# Sheet1.net
KiCad netlist of a schematic drawn in Altium Designer
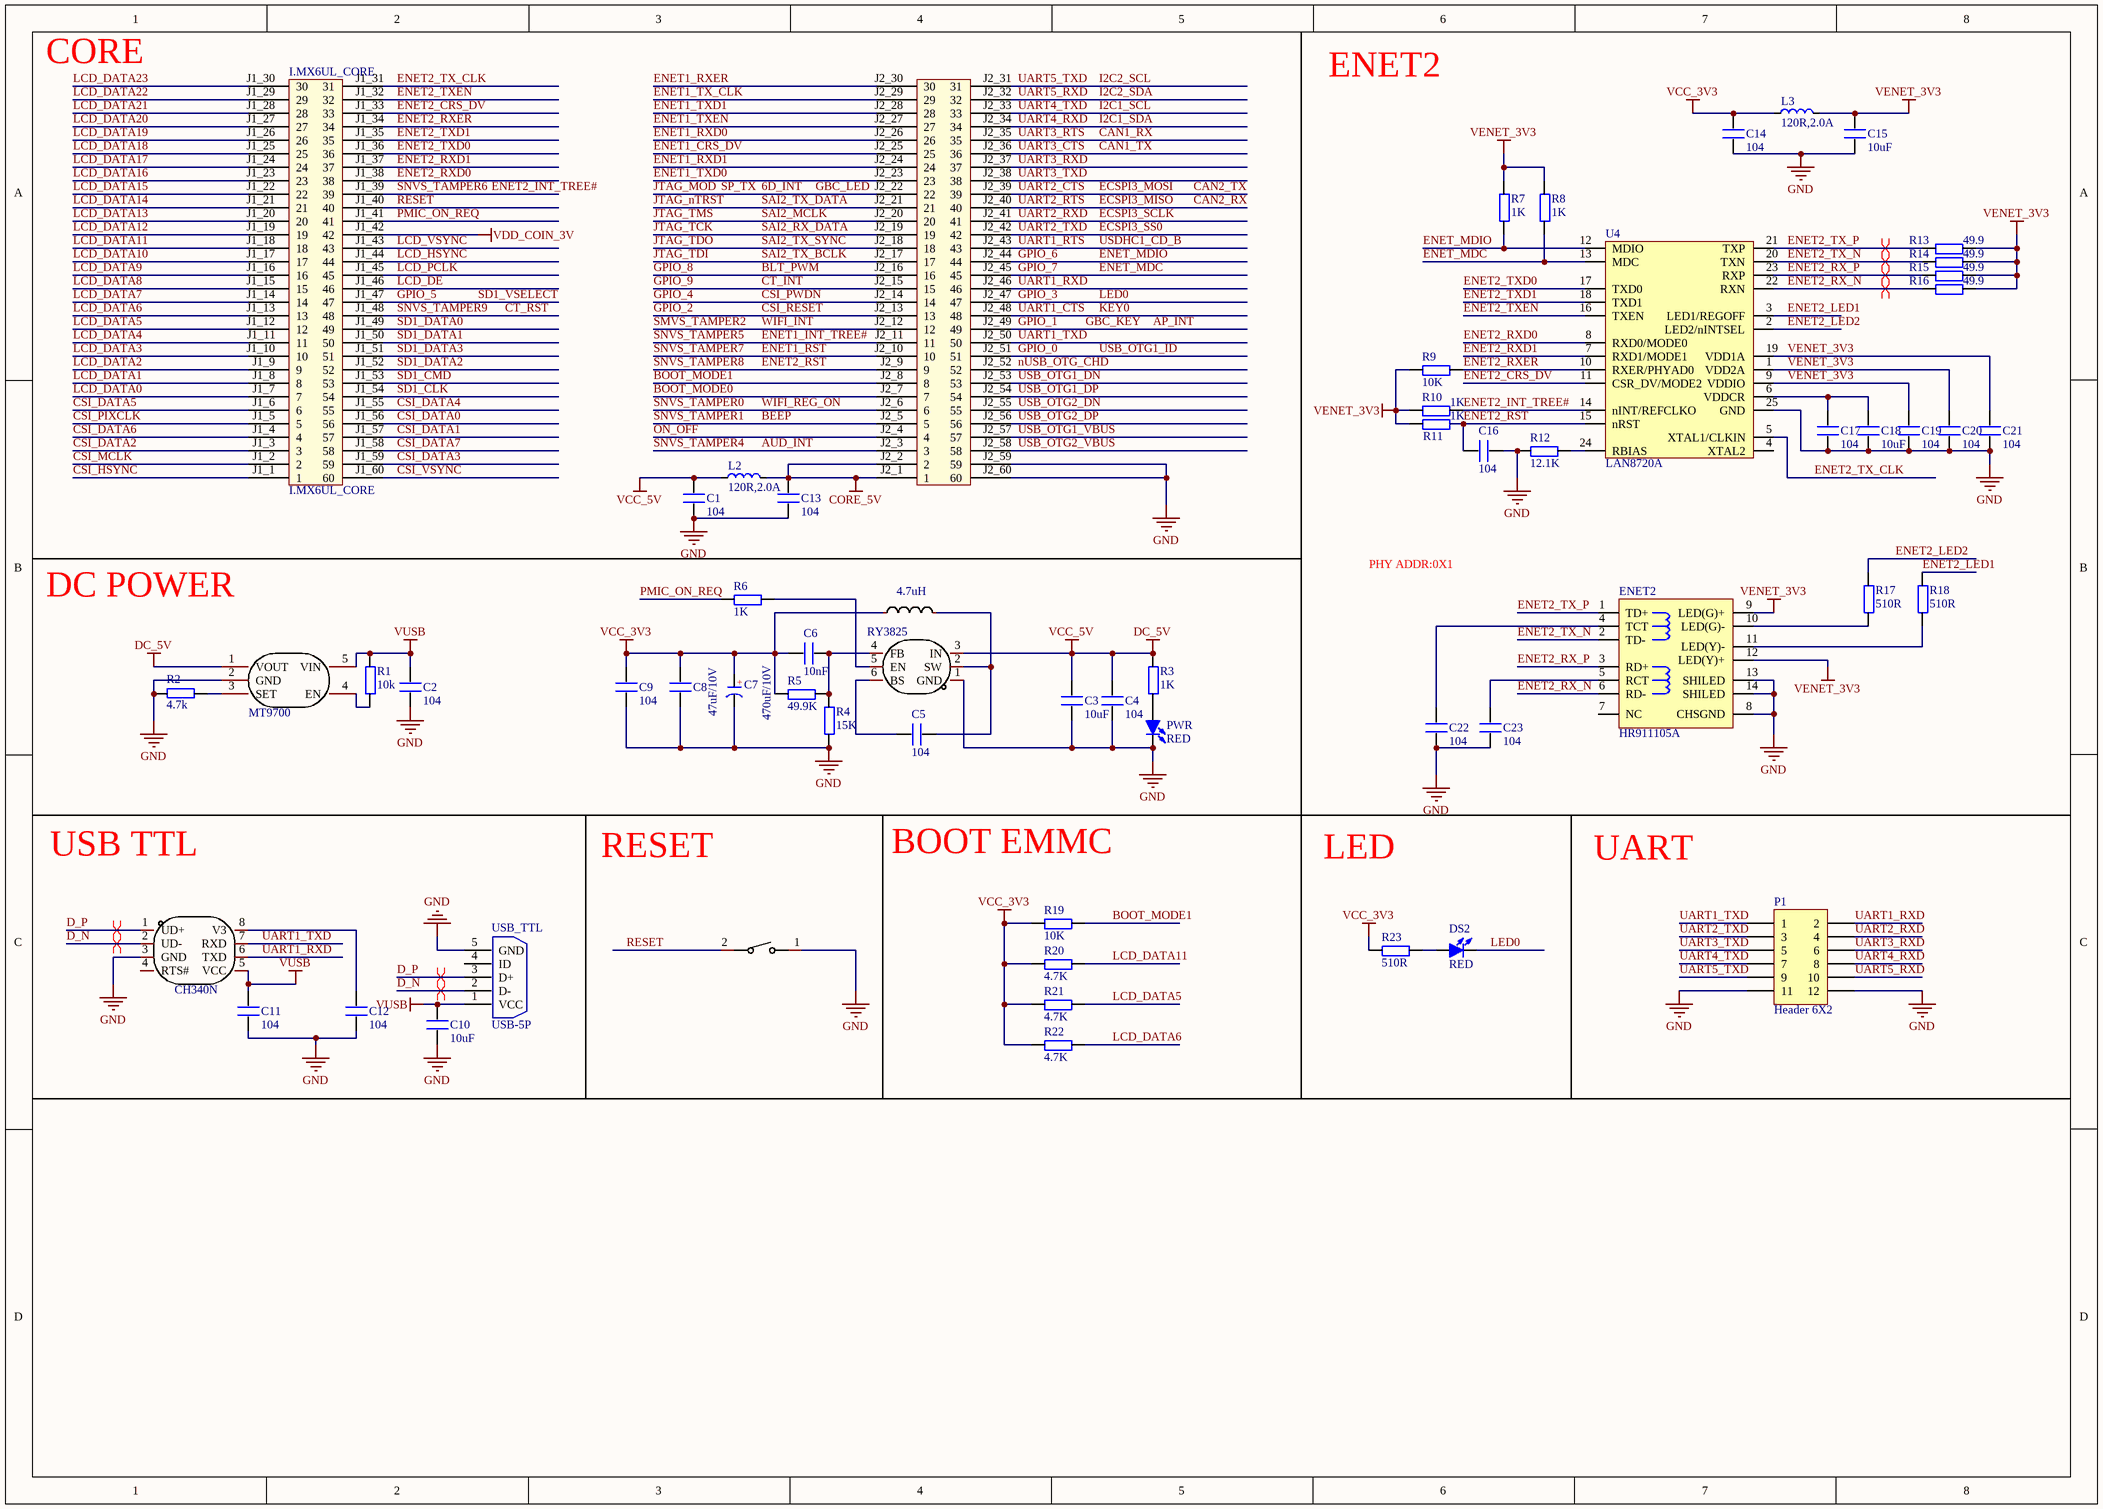
[diagram p0: Sheet1.SchDoc]

(export (version "E")
  (design (tool "Eeschema 10.0.6"))
  (components
    (comp (ref "1")
      (value "4.7uH")
      (footprint "IND-SMD_L5.4-W5.2_FXL0530")
      (description "4.7uH 5A")
      (fields (field (name "MANUFACTURER") "cjiang(长江微电)") (field (name "MANUFACTURER PART") "FXL0530-4R7-M"))
      (libsource (lib "LC_Components") (part "FXL0530-4R7-M"))
    )
    (comp (ref "C1") (value "104") (footprint "C 0603") (libsource (lib "IMX6UL_ALPHA(底板)_V2.0") (part "C")))
    (comp (ref "C2") (value "104") (footprint "C 0603") (libsource (lib "IMX6UL_ALPHA(底板)_V2.0") (part "C")))
    (comp (ref "C3") (value "10uF") (footprint "C 0603") (libsource (lib "IMX6UL_ALPHA(底板)_V2.0") (part "C")))
    (comp (ref "C4") (value "104") (footprint "C 0603") (libsource (lib "IMX6UL_ALPHA(底板)_V2.0") (part "C")))
    (comp (ref "C5") (value "104") (footprint "C 0603") (libsource (lib "IMX6UL_ALPHA(底板)_V2.0") (part "C")))
    (comp (ref "C6") (value "10nF") (footprint "C 0603") (libsource (lib "IMX6UL_ALPHA(底板)_V2.0") (part "C")))
    (comp (ref "C7")
      (value "470uF/10V")
      (footprint "CM D(6.3*7.7)")
      (description "贴片电解电容")
      (fields (field (name "版权归属") "源创客"))
      (libsource (lib "IMX6UL_ALPHA(底板)_V2.0") (part "C-CM"))
    )
    (comp (ref "C8")
      (value "47uF/10V")
      (footprint "1206")
      (libsource (lib "IMX6UL_ALPHA(底板)_V2.0") (part "C"))
    )
    (comp (ref "C9") (value "104") (footprint "C 0603") (libsource (lib "IMX6UL_ALPHA(底板)_V2.0") (part "C")))
    (comp (ref "C10")
      (value "10uF")
      (footprint "C 0603")
      (libsource (lib "IMX6UL_ALPHA(底板)_V2.0") (part "C"))
    )
    (comp (ref "C11") (value "104") (footprint "C 0603") (libsource (lib "IMX6UL_ALPHA(底板)_V2.0") (part "C")))
    (comp (ref "C12") (value "104") (footprint "C 0603") (libsource (lib "IMX6UL_ALPHA(底板)_V2.0") (part "C")))
    (comp (ref "C13") (value "104") (footprint "C 0603") (libsource (lib "IMX6UL_ALPHA(底板)_V2.0") (part "C")))
    (comp (ref "C14") (value "104") (footprint "C 0603") (libsource (lib "IMX6UL_ALPHA(底板)_V2.0") (part "C")))
    (comp (ref "C15")
      (value "10uF")
      (footprint "C 0603")
      (libsource (lib "IMX6UL_ALPHA(底板)_V2.0") (part "C"))
    )
    (comp (ref "C16") (value "104") (footprint "C 0603") (libsource (lib "IMX6UL_ALPHA(底板)_V2.0") (part "C")))
    (comp (ref "C17") (value "104") (footprint "C 0603") (libsource (lib "IMX6UL_ALPHA(底板)_V2.0") (part "C")))
    (comp (ref "C18")
      (value "10uF")
      (footprint "C 0603")
      (libsource (lib "IMX6UL_ALPHA(底板)_V2.0") (part "C"))
    )
    (comp (ref "C19") (value "104") (footprint "C 0603") (libsource (lib "IMX6UL_ALPHA(底板)_V2.0") (part "C")))
    (comp (ref "C20") (value "104") (footprint "C 0603") (libsource (lib "IMX6UL_ALPHA(底板)_V2.0") (part "C")))
    (comp (ref "C21") (value "104") (footprint "C 0603") (libsource (lib "IMX6UL_ALPHA(底板)_V2.0") (part "C")))
    (comp (ref "C22") (value "104") (footprint "C 0603") (libsource (lib "IMX6UL_ALPHA(底板)_V2.0") (part "C")))
    (comp (ref "C23") (value "104") (footprint "C 0603") (libsource (lib "IMX6UL_ALPHA(底板)_V2.0") (part "C")))
    (comp (ref "DS2")
      (value "RED")
      (footprint "LED 0603B")
      (description "贴片LED")
      (fields (field (name "版权归属") "源创客"))
      (libsource (lib "IMX6UL_ALPHA(底板)_V2.0") (part "LED-SMD"))
    )
    (comp (ref "ENET2")
      (value "HR911105A")
      (footprint "RJ-45A12")
      (description "带灯以太网接口")
      (fields (field (name "版权归属") "源创客"))
      (libsource (lib "IMX6UL_ALPHA(底板)_V2.0") (part "HR911105A"))
    )
    (comp (ref "I.MX6UL_CORE")
      (value "I.MX6UL_CORE")
      (footprint "I.MX6UL_CORE")
      (description "I.MX6UL核心板")
      (libsource (lib "IMX6UL_ALPHA(底板)_V2.0") (part "I.MX6UL核心板"))
    )
    (comp (ref "L2")
      (value "120R,2.0A")
      (footprint "L 0603")
      (description "小功率贴片电感磁珠")
      (fields (field (name "版权归属") "源创客"))
      (libsource (lib "IMX6UL_ALPHA(底板)_V2.0") (part "L"))
    )
    (comp (ref "L3")
      (value "120R,2.0A")
      (footprint "L 0603")
      (description "小功率贴片电感磁珠")
      (fields (field (name "版权归属") "源创客"))
      (libsource (lib "IMX6UL_ALPHA(底板)_V2.0") (part "L"))
    )
    (comp (ref "P1")
      (value "Header 6X2")
      (footprint "HDR2X6")
      (description "Header, 6-Pin, Dual row")
      (fields (field (name "PUBLISHER") "Altium Limited"))
      (libsource (lib "IMX6UL_ALPHA(底板)_V2.0") (part "Header 6X2"))
    )
    (comp (ref "PWR")
      (value "RED")
      (footprint "LED 0603B")
      (description "贴片LED")
      (fields (field (name "版权归属") "源创客"))
      (libsource (lib "IMX6UL_ALPHA(底板)_V2.0") (part "LED-SMD"))
    )
    (comp (ref "R1") (value "10k") (footprint "R 0603") (libsource (lib "IMX6UL_ALPHA(底板)_V2.0") (part "R")))
    (comp (ref "R2") (value "4.7k") (footprint "R 0603") (libsource (lib "IMX6UL_ALPHA(底板)_V2.0") (part "R")))
    (comp (ref "R3") (value "1K") (footprint "R 0603") (libsource (lib "IMX6UL_ALPHA(底板)_V2.0") (part "R")))
    (comp (ref "R4") (value "15K") (footprint "R 0603") (libsource (lib "IMX6UL_ALPHA(底板)_V2.0") (part "R")))
    (comp (ref "R5")
      (value "49.9K")
      (footprint "R 0603")
      (libsource (lib "IMX6UL_ALPHA(底板)_V2.0") (part "R"))
    )
    (comp (ref "R6") (value "1K") (footprint "R 0603") (libsource (lib "IMX6UL_ALPHA(底板)_V2.0") (part "R")))
    (comp (ref "R7") (value "1K") (footprint "R 0603") (libsource (lib "IMX6UL_ALPHA(底板)_V2.0") (part "R")))
    (comp (ref "R8") (value "1K") (footprint "R 0603") (libsource (lib "IMX6UL_ALPHA(底板)_V2.0") (part "R")))
    (comp (ref "R9") (value "10K") (footprint "R 0603") (libsource (lib "IMX6UL_ALPHA(底板)_V2.0") (part "R")))
    (comp (ref "R10") (value "1K") (footprint "R 0603") (libsource (lib "IMX6UL_ALPHA(底板)_V2.0") (part "R")))
    (comp (ref "R11") (value "1K") (footprint "R 0603") (libsource (lib "IMX6UL_ALPHA(底板)_V2.0") (part "R")))
    (comp (ref "R12")
      (value "12.1K")
      (footprint "R 0603")
      (libsource (lib "IMX6UL_ALPHA(底板)_V2.0") (part "R"))
    )
    (comp (ref "R13")
      (value "49.9")
      (footprint "R 0603")
      (libsource (lib "IMX6UL_ALPHA(底板)_V2.0") (part "R"))
    )
    (comp (ref "R14")
      (value "49.9")
      (footprint "R 0603")
      (libsource (lib "IMX6UL_ALPHA(底板)_V2.0") (part "R"))
    )
    (comp (ref "R15")
      (value "49.9")
      (footprint "R 0603")
      (libsource (lib "IMX6UL_ALPHA(底板)_V2.0") (part "R"))
    )
    (comp (ref "R16")
      (value "49.9")
      (footprint "R 0603")
      (libsource (lib "IMX6UL_ALPHA(底板)_V2.0") (part "R"))
    )
    (comp (ref "R17")
      (value "510R")
      (footprint "R 0603")
      (libsource (lib "IMX6UL_ALPHA(底板)_V2.0") (part "R"))
    )
    (comp (ref "R18")
      (value "510R")
      (footprint "R 0603")
      (libsource (lib "IMX6UL_ALPHA(底板)_V2.0") (part "R"))
    )
    (comp (ref "R19") (value "10K") (footprint "R 0603") (libsource (lib "IMX6UL_ALPHA(底板)_V2.0") (part "R")))
    (comp (ref "R20")
      (value "4.7K")
      (footprint "R 0603")
      (libsource (lib "IMX6UL_ALPHA(底板)_V2.0") (part "R"))
    )
    (comp (ref "R21")
      (value "4.7K")
      (footprint "R 0603")
      (libsource (lib "IMX6UL_ALPHA(底板)_V2.0") (part "R"))
    )
    (comp (ref "R22")
      (value "4.7K")
      (footprint "R 0603")
      (libsource (lib "IMX6UL_ALPHA(底板)_V2.0") (part "R"))
    )
    (comp (ref "R23")
      (value "510R")
      (footprint "R 0603")
      (libsource (lib "IMX6UL_ALPHA(底板)_V2.0") (part "R"))
    )
    (comp (ref "SW")
      (value "TS3625A-HT")
      (footprint "SW-SMD_L6.1-W3.7-LS7.9")
      (description "红头按键")
      (fields (field (name "MANUFACTURER") "SHOU HAN(首韩)"))
      (libsource (lib "LC_Components") (part "TS3625A-HT"))
    )
    (comp (ref "U1")
      (value "MT9700")
      (footprint "SOT-23-5_L3.0-W1.7-P0.95-LS2.8-BR")
      (fields (field (name "MANUFACTURER") "西安航天民芯"))
      (libsource (lib "LC_Components") (part "MT9700"))
    )
    (comp (ref "U2")
      (value "RY3825")
      (footprint "SOT-23-6_L2.9-W1.6-P0.95-LS2.8-BR")
      (fields (field (name "MANUFACTURER") "RYCHiP(蕊源)"))
      (libsource (lib "LC_Components") (part "RY3825"))
    )
    (comp (ref "U3")
      (value "CH340N")
      (footprint "SOP-8_L4.9-W3.9-P1.27-LS6.0-BL")
      (fields (field (name "DESIGNER") "U?"))
      (libsource (lib "LC_Components") (part "CH340N_C2977777"))
    )
    (comp (ref "U4")
      (value "LAN8720A")
      (footprint "QFN24")
      (description "ETH PHY")
      (libsource (lib "IMX6UL_ALPHA(底板)_V2.0") (part "LAN8720"))
    )
    (comp (ref "USB_TTL")
      (value "USB-5P")
      (footprint "USB-MINI-A")
      (description "微型USB母座")
      (fields (field (name "版权归属") "源创客"))
      (libsource (lib "IMX6UL_ALPHA(底板)_V2.0") (part "USB-5P"))
    )
  )
  (nets
    (net (code "1") (name "/6D_INT") (class "Default")
      (node (ref "I.MX6UL_CORE") (pin "J2_22") (pinfunction "22_J2_22") (pintype "passive"))
    )
    (net (code "2") (name "/AP_INT") (class "Default")
      (node (ref "I.MX6UL_CORE") (pin "J2_49") (pinfunction "49_J2_49") (pintype "passive"))
    )
    (net (code "3") (name "/AUD_INT") (class "Default")
      (node (ref "I.MX6UL_CORE") (pin "J2_3") (pinfunction "3_J2_3") (pintype "passive"))
    )
    (net (code "4") (name "/BEEP") (class "Default")
      (node (ref "I.MX6UL_CORE") (pin "J2_5") (pinfunction "5_J2_5") (pintype "passive"))
    )
    (net (code "5") (name "/BLT_PWM") (class "Default")
      (node (ref "I.MX6UL_CORE") (pin "J2_16") (pinfunction "16_J2_16") (pintype "passive"))
    )
    (net (code "6") (name "/BOOT_MODE0") (class "Default")
      (node (ref "I.MX6UL_CORE") (pin "J2_7") (pinfunction "7_J2_7") (pintype "passive"))
    )
    (net (code "7") (name "/BOOT_MODE1") (class "Default")
      (node (ref "I.MX6UL_CORE") (pin "J2_8") (pinfunction "8_J2_8") (pintype "passive"))
      (node (ref "R19") (pin "2") (pintype "passive"))
    )
    (net (code "8") (name "/CAN1_RX") (class "Default")
      (node (ref "I.MX6UL_CORE") (pin "J2_35") (pinfunction "35_J2_35") (pintype "passive"))
    )
    (net (code "9") (name "/CAN1_TX") (class "Default")
      (node (ref "I.MX6UL_CORE") (pin "J2_36") (pinfunction "36_J2_36") (pintype "passive"))
    )
    (net (code "10") (name "/CAN2_RX") (class "Default")
      (node (ref "I.MX6UL_CORE") (pin "J2_40") (pinfunction "40_J2_40") (pintype "passive"))
    )
    (net (code "11") (name "/CAN2_TX") (class "Default")
      (node (ref "I.MX6UL_CORE") (pin "J2_39") (pinfunction "39_J2_39") (pintype "passive"))
    )
    (net (code "12") (name "/CSI_DATA0") (class "Default")
      (node (ref "I.MX6UL_CORE") (pin "J1_56") (pinfunction "56_J1_56") (pintype "passive"))
    )
    (net (code "13") (name "/CSI_DATA1") (class "Default")
      (node (ref "I.MX6UL_CORE") (pin "J1_57") (pinfunction "57_J1_57") (pintype "passive"))
    )
    (net (code "14") (name "/CSI_DATA2") (class "Default")
      (node (ref "I.MX6UL_CORE") (pin "J1_3") (pinfunction "3_J1_3") (pintype "passive"))
    )
    (net (code "15") (name "/CSI_DATA3") (class "Default")
      (node (ref "I.MX6UL_CORE") (pin "J1_59") (pinfunction "59_J1_59") (pintype "passive"))
    )
    (net (code "16") (name "/CSI_DATA4") (class "Default")
      (node (ref "I.MX6UL_CORE") (pin "J1_55") (pinfunction "55_J1_55") (pintype "passive"))
    )
    (net (code "17") (name "/CSI_DATA5") (class "Default")
      (node (ref "I.MX6UL_CORE") (pin "J1_6") (pinfunction "6_J1_6") (pintype "passive"))
    )
    (net (code "18") (name "/CSI_DATA6") (class "Default")
      (node (ref "I.MX6UL_CORE") (pin "J1_4") (pinfunction "4_J1_4") (pintype "passive"))
    )
    (net (code "19") (name "/CSI_DATA7") (class "Default")
      (node (ref "I.MX6UL_CORE") (pin "J1_58") (pinfunction "58_J1_58") (pintype "passive"))
    )
    (net (code "20") (name "/CSI_HSYNC") (class "Default")
      (node (ref "I.MX6UL_CORE") (pin "J1_1") (pinfunction "1_J1_1") (pintype "passive"))
    )
    (net (code "21") (name "/CSI_MCLK") (class "Default")
      (node (ref "I.MX6UL_CORE") (pin "J1_2") (pinfunction "2_J1_2") (pintype "passive"))
    )
    (net (code "22") (name "/CSI_PIXCLK") (class "Default")
      (node (ref "I.MX6UL_CORE") (pin "J1_5") (pinfunction "5_J1_5") (pintype "passive"))
    )
    (net (code "23") (name "/CSI_PWDN") (class "Default")
      (node (ref "I.MX6UL_CORE") (pin "J2_14") (pinfunction "14_J2_14") (pintype "passive"))
    )
    (net (code "24") (name "/CSI_RESET") (class "Default")
      (node (ref "I.MX6UL_CORE") (pin "J2_13") (pinfunction "13_J2_13") (pintype "passive"))
    )
    (net (code "25") (name "/CSI_VSYNC") (class "Default")
      (node (ref "I.MX6UL_CORE") (pin "J1_60") (pinfunction "60_J1_60") (pintype "passive"))
    )
    (net (code "26") (name "/CT_INT") (class "Default")
      (node (ref "I.MX6UL_CORE") (pin "J2_15") (pinfunction "15_J2_15") (pintype "passive"))
    )
    (net (code "27") (name "/CT_RST") (class "Default")
      (node (ref "I.MX6UL_CORE") (pin "J1_48") (pinfunction "48_J1_48") (pintype "passive"))
    )
    (net (code "28") (name "/D_N") (class "Default")
      (node (ref "U3") (pin "2") (pinfunction "UD-_2") (pintype "passive"))
      (node (ref "USB_TTL") (pin "2") (pinfunction "D-_2") (pintype "passive"))
    )
    (net (code "29") (name "/D_P") (class "Default")
      (node (ref "U3") (pin "1") (pinfunction "UD+_1") (pintype "passive"))
      (node (ref "USB_TTL") (pin "3") (pinfunction "D+_3") (pintype "passive"))
    )
    (net (code "30") (name "/ECSPI3_SCLK") (class "Default")
      (node (ref "I.MX6UL_CORE") (pin "J2_41") (pinfunction "41_J2_41") (pintype "passive"))
      (node (ref "P1") (pin "4") (pinfunction "4_4") (pintype "passive"))
    )
    (net (code "31") (name "/ECSPI3_SS0") (class "Default")
      (node (ref "I.MX6UL_CORE") (pin "J2_42") (pinfunction "42_J2_42") (pintype "passive"))
      (node (ref "P1") (pin "3") (pinfunction "3_3") (pintype "passive"))
    )
    (net (code "32") (name "/ENET1_CRS_DV") (class "Default")
      (node (ref "I.MX6UL_CORE") (pin "J2_25") (pinfunction "25_J2_25") (pintype "passive"))
    )
    (net (code "33") (name "/ENET1_INT_TREE#") (class "Default")
      (node (ref "I.MX6UL_CORE") (pin "J2_11") (pinfunction "11_J2_11") (pintype "passive"))
    )
    (net (code "34") (name "/ENET1_RST") (class "Default")
      (node (ref "I.MX6UL_CORE") (pin "J2_10") (pinfunction "10_J2_10") (pintype "passive"))
    )
    (net (code "35") (name "/ENET1_RXD0") (class "Default")
      (node (ref "I.MX6UL_CORE") (pin "J2_26") (pinfunction "26_J2_26") (pintype "passive"))
    )
    (net (code "36") (name "/ENET1_RXD1") (class "Default")
      (node (ref "I.MX6UL_CORE") (pin "J2_24") (pinfunction "24_J2_24") (pintype "passive"))
    )
    (net (code "37") (name "/ENET1_RXER") (class "Default")
      (node (ref "I.MX6UL_CORE") (pin "J2_30") (pinfunction "30_J2_30") (pintype "passive"))
    )
    (net (code "38") (name "/ENET1_TXD0") (class "Default")
      (node (ref "I.MX6UL_CORE") (pin "J2_23") (pinfunction "23_J2_23") (pintype "passive"))
    )
    (net (code "39") (name "/ENET1_TXD1") (class "Default")
      (node (ref "I.MX6UL_CORE") (pin "J2_28") (pinfunction "28_J2_28") (pintype "passive"))
    )
    (net (code "40") (name "/ENET1_TXEN") (class "Default")
      (node (ref "I.MX6UL_CORE") (pin "J2_27") (pinfunction "27_J2_27") (pintype "passive"))
    )
    (net (code "41") (name "/ENET1_TX_CLK") (class "Default")
      (node (ref "I.MX6UL_CORE") (pin "J2_29") (pinfunction "29_J2_29") (pintype "passive"))
    )
    (net (code "42") (name "/ENET2_CRS_DV") (class "Default")
      (node (ref "I.MX6UL_CORE") (pin "J1_33") (pinfunction "33_J1_33") (pintype "passive"))
      (node (ref "U4") (pin "11") (pinfunction "CSR_DV/MODE2_11") (pintype "passive"))
    )
    (net (code "43") (name "/ENET2_INT_TREE#") (class "Default")
      (node (ref "I.MX6UL_CORE") (pin "J1_39") (pinfunction "39_J1_39") (pintype "passive"))
      (node (ref "R10") (pin "2") (pintype "passive"))
      (node (ref "U4") (pin "14") (pinfunction "nINT/REFCLKO_14") (pintype "passive"))
    )
    (net (code "44") (name "/ENET2_LED1") (class "Default")
      (node (ref "R18") (pin "2") (pintype "passive"))
      (node (ref "U4") (pin "3") (pinfunction "LED1/REGOFF_3") (pintype "passive"))
    )
    (net (code "45") (name "/ENET2_LED2") (class "Default")
      (node (ref "R17") (pin "2") (pintype "passive"))
      (node (ref "U4") (pin "2") (pinfunction "LED2/nINTSEL_2") (pintype "passive"))
    )
    (net (code "46") (name "/ENET2_RST") (class "Default")
      (node (ref "C16") (pin "1") (pintype "passive"))
      (node (ref "I.MX6UL_CORE") (pin "J2_9") (pinfunction "9_J2_9") (pintype "passive"))
      (node (ref "R11") (pin "2") (pintype "passive"))
      (node (ref "U4") (pin "15") (pinfunction "nRST_15") (pintype "passive"))
    )
    (net (code "47") (name "/ENET2_RXD0") (class "Default")
      (node (ref "I.MX6UL_CORE") (pin "J1_38") (pinfunction "38_J1_38") (pintype "passive"))
      (node (ref "U4") (pin "8") (pinfunction "RXD0/MODE0_8") (pintype "passive"))
    )
    (net (code "48") (name "/ENET2_RXD1") (class "Default")
      (node (ref "I.MX6UL_CORE") (pin "J1_37") (pinfunction "37_J1_37") (pintype "passive"))
      (node (ref "U4") (pin "7") (pinfunction "RXD1/MODE1_7") (pintype "passive"))
    )
    (net (code "49") (name "/ENET2_RXER") (class "Default")
      (node (ref "I.MX6UL_CORE") (pin "J1_34") (pinfunction "34_J1_34") (pintype "passive"))
      (node (ref "R9") (pin "2") (pintype "passive"))
      (node (ref "U4") (pin "10") (pinfunction "RXER/PHYAD0_10") (pintype "passive"))
    )
    (net (code "50") (name "/ENET2_RX_N") (class "Default")
      (node (ref "ENET2") (pin "6") (pinfunction "RD-_6") (pintype "passive"))
      (node (ref "R16") (pin "1") (pintype "passive"))
      (node (ref "U4") (pin "22") (pinfunction "RXN_22") (pintype "passive"))
    )
    (net (code "51") (name "/ENET2_RX_P") (class "Default")
      (node (ref "ENET2") (pin "3") (pinfunction "RD+_3") (pintype "passive"))
      (node (ref "R15") (pin "1") (pintype "passive"))
      (node (ref "U4") (pin "23") (pinfunction "RXP_23") (pintype "passive"))
    )
    (net (code "52") (name "/ENET2_TXD0") (class "Default")
      (node (ref "I.MX6UL_CORE") (pin "J1_36") (pinfunction "36_J1_36") (pintype "passive"))
      (node (ref "U4") (pin "17") (pinfunction "TXD0_17") (pintype "passive"))
    )
    (net (code "53") (name "/ENET2_TXD1") (class "Default")
      (node (ref "I.MX6UL_CORE") (pin "J1_35") (pinfunction "35_J1_35") (pintype "passive"))
      (node (ref "U4") (pin "18") (pinfunction "TXD1_18") (pintype "passive"))
    )
    (net (code "54") (name "/ENET2_TXEN") (class "Default")
      (node (ref "I.MX6UL_CORE") (pin "J1_32") (pinfunction "32_J1_32") (pintype "passive"))
      (node (ref "U4") (pin "16") (pinfunction "TXEN_16") (pintype "passive"))
    )
    (net (code "55") (name "/ENET2_TX_CLK") (class "Default")
      (node (ref "I.MX6UL_CORE") (pin "J1_31") (pinfunction "31_J1_31") (pintype "passive"))
      (node (ref "U4") (pin "5") (pinfunction "XTAL1/CLKIN_5") (pintype "passive"))
    )
    (net (code "56") (name "/ENET2_TX_N") (class "Default")
      (node (ref "ENET2") (pin "2") (pinfunction "TD-_2") (pintype "passive"))
      (node (ref "R14") (pin "1") (pintype "passive"))
      (node (ref "U4") (pin "20") (pinfunction "TXN_20") (pintype "passive"))
    )
    (net (code "57") (name "/ENET2_TX_P") (class "Default")
      (node (ref "ENET2") (pin "1") (pinfunction "TD+_1") (pintype "passive"))
      (node (ref "R13") (pin "1") (pintype "passive"))
      (node (ref "U4") (pin "21") (pinfunction "TXP_21") (pintype "passive"))
    )
    (net (code "58") (name "/ENET_MDC") (class "Default")
      (node (ref "I.MX6UL_CORE") (pin "J2_45") (pinfunction "45_J2_45") (pintype "passive"))
      (node (ref "R8") (pin "1") (pintype "passive"))
      (node (ref "U4") (pin "13") (pinfunction "MDC_13") (pintype "passive"))
    )
    (net (code "59") (name "/ENET_MDIO") (class "Default")
      (node (ref "I.MX6UL_CORE") (pin "J2_44") (pinfunction "44_J2_44") (pintype "passive"))
      (node (ref "R7") (pin "1") (pintype "passive"))
      (node (ref "U4") (pin "12") (pinfunction "MDIO_12") (pintype "passive"))
    )
    (net (code "60") (name "/GPIO_0") (class "Default")
      (node (ref "I.MX6UL_CORE") (pin "J2_51") (pinfunction "51_J2_51") (pintype "passive"))
    )
    (net (code "61") (name "/GPIO_3") (class "Default")
      (node (ref "DS2") (pin "2") (pinfunction "K_2") (pintype "passive"))
      (node (ref "I.MX6UL_CORE") (pin "J2_47") (pinfunction "47_J2_47") (pintype "passive"))
    )
    (net (code "62") (name "/GPIO_5") (class "Default")
      (node (ref "I.MX6UL_CORE") (pin "J1_47") (pinfunction "47_J1_47") (pintype "passive"))
    )
    (net (code "63") (name "/I2C1_SCL") (class "Default")
      (node (ref "I.MX6UL_CORE") (pin "J2_33") (pinfunction "33_J2_33") (pintype "passive"))
      (node (ref "P1") (pin "7") (pinfunction "7_7") (pintype "passive"))
    )
    (net (code "64") (name "/I2C1_SDA") (class "Default")
      (node (ref "I.MX6UL_CORE") (pin "J2_34") (pinfunction "34_J2_34") (pintype "passive"))
      (node (ref "P1") (pin "8") (pinfunction "8_8") (pintype "passive"))
    )
    (net (code "65") (name "/I2C2_SCL") (class "Default")
      (node (ref "I.MX6UL_CORE") (pin "J2_31") (pinfunction "31_J2_31") (pintype "passive"))
      (node (ref "P1") (pin "9") (pinfunction "9_9") (pintype "passive"))
    )
    (net (code "66") (name "/I2C2_SDA") (class "Default")
      (node (ref "I.MX6UL_CORE") (pin "J2_32") (pinfunction "32_J2_32") (pintype "passive"))
      (node (ref "P1") (pin "10") (pinfunction "10_10") (pintype "passive"))
    )
    (net (code "67") (name "/JTAG_TCK") (class "Default")
      (node (ref "I.MX6UL_CORE") (pin "J2_19") (pinfunction "19_J2_19") (pintype "passive"))
    )
    (net (code "68") (name "/JTAG_TDI") (class "Default")
      (node (ref "I.MX6UL_CORE") (pin "J2_17") (pinfunction "17_J2_17") (pintype "passive"))
    )
    (net (code "69") (name "/JTAG_TDO") (class "Default")
      (node (ref "I.MX6UL_CORE") (pin "J2_18") (pinfunction "18_J2_18") (pintype "passive"))
    )
    (net (code "70") (name "/JTAG_TMS") (class "Default")
      (node (ref "I.MX6UL_CORE") (pin "J2_20") (pinfunction "20_J2_20") (pintype "passive"))
    )
    (net (code "71") (name "/JTAG_nTRST") (class "Default")
      (node (ref "I.MX6UL_CORE") (pin "J2_21") (pinfunction "21_J2_21") (pintype "passive"))
    )
    (net (code "72") (name "/KEY0") (class "Default")
      (node (ref "I.MX6UL_CORE") (pin "J2_48") (pinfunction "48_J2_48") (pintype "passive"))
    )
    (net (code "73") (name "/LCD_DATA0") (class "Default")
      (node (ref "I.MX6UL_CORE") (pin "J1_7") (pinfunction "7_J1_7") (pintype "passive"))
    )
    (net (code "74") (name "/LCD_DATA1") (class "Default")
      (node (ref "I.MX6UL_CORE") (pin "J1_8") (pinfunction "8_J1_8") (pintype "passive"))
    )
    (net (code "75") (name "/LCD_DATA2") (class "Default")
      (node (ref "I.MX6UL_CORE") (pin "J1_9") (pinfunction "9_J1_9") (pintype "passive"))
    )
    (net (code "76") (name "/LCD_DATA3") (class "Default")
      (node (ref "I.MX6UL_CORE") (pin "J1_10") (pinfunction "10_J1_10") (pintype "passive"))
    )
    (net (code "77") (name "/LCD_DATA4") (class "Default")
      (node (ref "I.MX6UL_CORE") (pin "J1_11") (pinfunction "11_J1_11") (pintype "passive"))
    )
    (net (code "78") (name "/LCD_DATA5") (class "Default")
      (node (ref "I.MX6UL_CORE") (pin "J1_12") (pinfunction "12_J1_12") (pintype "passive"))
      (node (ref "R21") (pin "2") (pintype "passive"))
    )
    (net (code "79") (name "/LCD_DATA6") (class "Default")
      (node (ref "I.MX6UL_CORE") (pin "J1_13") (pinfunction "13_J1_13") (pintype "passive"))
      (node (ref "R22") (pin "2") (pintype "passive"))
    )
    (net (code "80") (name "/LCD_DATA7") (class "Default")
      (node (ref "I.MX6UL_CORE") (pin "J1_14") (pinfunction "14_J1_14") (pintype "passive"))
    )
    (net (code "81") (name "/LCD_DATA8") (class "Default")
      (node (ref "I.MX6UL_CORE") (pin "J1_15") (pinfunction "15_J1_15") (pintype "passive"))
    )
    (net (code "82") (name "/LCD_DATA9") (class "Default")
      (node (ref "I.MX6UL_CORE") (pin "J1_16") (pinfunction "16_J1_16") (pintype "passive"))
    )
    (net (code "83") (name "/LCD_DATA10") (class "Default")
      (node (ref "I.MX6UL_CORE") (pin "J1_17") (pinfunction "17_J1_17") (pintype "passive"))
    )
    (net (code "84") (name "/LCD_DATA11") (class "Default")
      (node (ref "I.MX6UL_CORE") (pin "J1_18") (pinfunction "18_J1_18") (pintype "passive"))
      (node (ref "R20") (pin "2") (pintype "passive"))
    )
    (net (code "85") (name "/LCD_DATA12") (class "Default")
      (node (ref "I.MX6UL_CORE") (pin "J1_19") (pinfunction "19_J1_19") (pintype "passive"))
    )
    (net (code "86") (name "/LCD_DATA13") (class "Default")
      (node (ref "I.MX6UL_CORE") (pin "J1_20") (pinfunction "20_J1_20") (pintype "passive"))
    )
    (net (code "87") (name "/LCD_DATA14") (class "Default")
      (node (ref "I.MX6UL_CORE") (pin "J1_21") (pinfunction "21_J1_21") (pintype "passive"))
    )
    (net (code "88") (name "/LCD_DATA15") (class "Default")
      (node (ref "I.MX6UL_CORE") (pin "J1_22") (pinfunction "22_J1_22") (pintype "passive"))
    )
    (net (code "89") (name "/LCD_DATA16") (class "Default")
      (node (ref "I.MX6UL_CORE") (pin "J1_23") (pinfunction "23_J1_23") (pintype "passive"))
    )
    (net (code "90") (name "/LCD_DATA17") (class "Default")
      (node (ref "I.MX6UL_CORE") (pin "J1_24") (pinfunction "24_J1_24") (pintype "passive"))
    )
    (net (code "91") (name "/LCD_DATA18") (class "Default")
      (node (ref "I.MX6UL_CORE") (pin "J1_25") (pinfunction "25_J1_25") (pintype "passive"))
    )
    (net (code "92") (name "/LCD_DATA19") (class "Default")
      (node (ref "I.MX6UL_CORE") (pin "J1_26") (pinfunction "26_J1_26") (pintype "passive"))
    )
    (net (code "93") (name "/LCD_DATA20") (class "Default")
      (node (ref "I.MX6UL_CORE") (pin "J1_27") (pinfunction "27_J1_27") (pintype "passive"))
    )
    (net (code "94") (name "/LCD_DATA21") (class "Default")
      (node (ref "I.MX6UL_CORE") (pin "J1_28") (pinfunction "28_J1_28") (pintype "passive"))
    )
    (net (code "95") (name "/LCD_DATA22") (class "Default")
      (node (ref "I.MX6UL_CORE") (pin "J1_29") (pinfunction "29_J1_29") (pintype "passive"))
    )
    (net (code "96") (name "/LCD_DATA23") (class "Default")
      (node (ref "I.MX6UL_CORE") (pin "J1_30") (pinfunction "30_J1_30") (pintype "passive"))
    )
    (net (code "97") (name "/LCD_DE") (class "Default")
      (node (ref "I.MX6UL_CORE") (pin "J1_46") (pinfunction "46_J1_46") (pintype "passive"))
    )
    (net (code "98") (name "/LCD_HSYNC") (class "Default")
      (node (ref "I.MX6UL_CORE") (pin "J1_44") (pinfunction "44_J1_44") (pintype "passive"))
    )
    (net (code "99") (name "/LCD_PCLK") (class "Default")
      (node (ref "I.MX6UL_CORE") (pin "J1_45") (pinfunction "45_J1_45") (pintype "passive"))
    )
    (net (code "100") (name "/LCD_VSYNC") (class "Default")
      (node (ref "I.MX6UL_CORE") (pin "J1_43") (pinfunction "43_J1_43") (pintype "passive"))
    )
    (net (code "101") (name "/ON_OFF") (class "Default")
      (node (ref "I.MX6UL_CORE") (pin "J2_4") (pinfunction "4_J2_4") (pintype "passive"))
    )
    (net (code "102") (name "/PMIC_ON_REQ") (class "Default")
      (node (ref "I.MX6UL_CORE") (pin "J1_41") (pinfunction "41_J1_41") (pintype "passive"))
      (node (ref "R6") (pin "1") (pintype "passive"))
    )
    (net (code "103") (name "/RESET") (class "Default")
      (node (ref "I.MX6UL_CORE") (pin "J1_40") (pinfunction "40_J1_40") (pintype "passive"))
      (node (ref "SW") (pin "2") (pinfunction "B_2") (pintype "passive"))
    )
    (net (code "104") (name "/SD1_CLK") (class "Default")
      (node (ref "I.MX6UL_CORE") (pin "J1_54") (pinfunction "54_J1_54") (pintype "passive"))
    )
    (net (code "105") (name "/SD1_CMD") (class "Default")
      (node (ref "I.MX6UL_CORE") (pin "J1_53") (pinfunction "53_J1_53") (pintype "passive"))
    )
    (net (code "106") (name "/SD1_DATA0") (class "Default")
      (node (ref "I.MX6UL_CORE") (pin "J1_49") (pinfunction "49_J1_49") (pintype "passive"))
    )
    (net (code "107") (name "/SD1_DATA1") (class "Default")
      (node (ref "I.MX6UL_CORE") (pin "J1_50") (pinfunction "50_J1_50") (pintype "passive"))
    )
    (net (code "108") (name "/SD1_DATA2") (class "Default")
      (node (ref "I.MX6UL_CORE") (pin "J1_52") (pinfunction "52_J1_52") (pintype "passive"))
    )
    (net (code "109") (name "/SD1_DATA3") (class "Default")
      (node (ref "I.MX6UL_CORE") (pin "J1_51") (pinfunction "51_J1_51") (pintype "passive"))
    )
    (net (code "110") (name "/SMVS_TAMPER2") (class "Default")
      (node (ref "I.MX6UL_CORE") (pin "J2_12") (pinfunction "12_J2_12") (pintype "passive"))
    )
    (net (code "111") (name "/SNVS_TAMPER0") (class "Default")
      (node (ref "I.MX6UL_CORE") (pin "J2_6") (pinfunction "6_J2_6") (pintype "passive"))
    )
    (net (code "112") (name "/UART1_RTS") (class "Default")
      (node (ref "I.MX6UL_CORE") (pin "J2_43") (pinfunction "43_J2_43") (pintype "passive"))
    )
    (net (code "113") (name "/UART1_RXD") (class "Default")
      (node (ref "I.MX6UL_CORE") (pin "J2_46") (pinfunction "46_J2_46") (pintype "passive"))
      (node (ref "P1") (pin "2") (pinfunction "2_2") (pintype "passive"))
      (node (ref "U3") (pin "6") (pinfunction "TXD_6") (pintype "passive"))
    )
    (net (code "114") (name "/UART1_TXD") (class "Default")
      (node (ref "I.MX6UL_CORE") (pin "J2_50") (pinfunction "50_J2_50") (pintype "passive"))
      (node (ref "P1") (pin "1") (pinfunction "1_1") (pintype "passive"))
      (node (ref "U3") (pin "7") (pinfunction "RXD_7") (pintype "passive"))
    )
    (net (code "115") (name "/UART3_RXD") (class "Default")
      (node (ref "I.MX6UL_CORE") (pin "J2_37") (pinfunction "37_J2_37") (pintype "passive"))
      (node (ref "P1") (pin "6") (pinfunction "6_6") (pintype "passive"))
    )
    (net (code "116") (name "/UART3_TXD") (class "Default")
      (node (ref "I.MX6UL_CORE") (pin "J2_38") (pinfunction "38_J2_38") (pintype "passive"))
      (node (ref "P1") (pin "5") (pinfunction "5_5") (pintype "passive"))
    )
    (net (code "117") (name "/USB_OTG1_DN") (class "Default")
      (node (ref "I.MX6UL_CORE") (pin "J2_53") (pinfunction "53_J2_53") (pintype "passive"))
    )
    (net (code "118") (name "/USB_OTG1_DP") (class "Default")
      (node (ref "I.MX6UL_CORE") (pin "J2_54") (pinfunction "54_J2_54") (pintype "passive"))
    )
    (net (code "119") (name "/USB_OTG1_VBUS") (class "Default")
      (node (ref "I.MX6UL_CORE") (pin "J2_57") (pinfunction "57_J2_57") (pintype "passive"))
    )
    (net (code "120") (name "/USB_OTG2_DN") (class "Default")
      (node (ref "I.MX6UL_CORE") (pin "J2_55") (pinfunction "55_J2_55") (pintype "passive"))
    )
    (net (code "121") (name "/USB_OTG2_DP") (class "Default")
      (node (ref "I.MX6UL_CORE") (pin "J2_56") (pinfunction "56_J2_56") (pintype "passive"))
    )
    (net (code "122") (name "/USB_OTG2_VBUS") (class "Default")
      (node (ref "I.MX6UL_CORE") (pin "J2_58") (pinfunction "58_J2_58") (pintype "passive"))
    )
    (net (code "123") (name "/nUSB_OTG_CHD") (class "Default")
      (node (ref "I.MX6UL_CORE") (pin "J2_52") (pinfunction "52_J2_52") (pintype "passive"))
    )
    (net (code "124") (name "CORE_5V") (class "Default")
      (node (ref "C13") (pin "2") (pintype "passive"))
      (node (ref "I.MX6UL_CORE") (pin "J2_1") (pinfunction "1_J2_1") (pintype "passive"))
      (node (ref "I.MX6UL_CORE") (pin "J2_2") (pinfunction "2_J2_2") (pintype "passive"))
      (node (ref "L2") (pin "2") (pinfunction "2_2") (pintype "passive"))
    )
    (net (code "125") (name "DC_5V") (class "Default")
      (node (ref "C1") (pin "2") (pintype "passive"))
      (node (ref "C3") (pin "2") (pintype "passive"))
      (node (ref "C4") (pin "2") (pintype "passive"))
      (node (ref "L2") (pin "1") (pinfunction "1_1") (pintype "passive"))
      (node (ref "R3") (pin "2") (pintype "passive"))
      (node (ref "U1") (pin "1") (pinfunction "VOUT_1") (pintype "passive"))
      (node (ref "U2") (pin "3") (pinfunction "IN_3") (pintype "passive"))
    )
    (net (code "126") (name "GND") (class "Default")
      (node (ref "C1") (pin "1") (pintype "passive"))
      (node (ref "C10") (pin "1") (pintype "passive"))
      (node (ref "C11") (pin "1") (pintype "passive"))
      (node (ref "C12") (pin "1") (pintype "passive"))
      (node (ref "C13") (pin "1") (pintype "passive"))
      (node (ref "C14") (pin "1") (pintype "passive"))
      (node (ref "C15") (pin "1") (pintype "passive"))
      (node (ref "C16") (pin "2") (pintype "passive"))
      (node (ref "C17") (pin "1") (pintype "passive"))
      (node (ref "C18") (pin "1") (pintype "passive"))
      (node (ref "C19") (pin "1") (pintype "passive"))
      (node (ref "C2") (pin "1") (pintype "passive"))
      (node (ref "C20") (pin "1") (pintype "passive"))
      (node (ref "C21") (pin "1") (pintype "passive"))
      (node (ref "C22") (pin "1") (pintype "passive"))
      (node (ref "C23") (pin "1") (pintype "passive"))
      (node (ref "C3") (pin "1") (pintype "passive"))
      (node (ref "C4") (pin "1") (pintype "passive"))
      (node (ref "C7") (pin "2") (pinfunction "K_2") (pintype "passive"))
      (node (ref "C8") (pin "1") (pintype "passive"))
      (node (ref "C9") (pin "1") (pintype "passive"))
      (node (ref "ENET2") (pin "13") (pinfunction "SHILED_13") (pintype "passive"))
      (node (ref "ENET2") (pin "14") (pinfunction "SHILED_14") (pintype "passive"))
      (node (ref "ENET2") (pin "8") (pinfunction "CHSGND_8") (pintype "passive"))
      (node (ref "I.MX6UL_CORE") (pin "J2_59") (pinfunction "59_J2_59") (pintype "passive"))
      (node (ref "I.MX6UL_CORE") (pin "J2_60") (pinfunction "60_J2_60") (pintype "passive"))
      (node (ref "P1") (pin "11") (pinfunction "11_11") (pintype "passive"))
      (node (ref "P1") (pin "12") (pinfunction "12_12") (pintype "passive"))
      (node (ref "PWR") (pin "2") (pinfunction "K_2") (pintype "passive"))
      (node (ref "R12") (pin "1") (pintype "passive"))
      (node (ref "R2") (pin "2") (pintype "passive"))
      (node (ref "R4") (pin "1") (pintype "passive"))
      (node (ref "SW") (pin "1") (pinfunction "A_1") (pintype "passive"))
      (node (ref "U1") (pin "2") (pinfunction "GND_2") (pintype "passive"))
      (node (ref "U2") (pin "1") (pinfunction "GND_1") (pintype "passive"))
      (node (ref "U3") (pin "3") (pinfunction "GND_3") (pintype "passive"))
      (node (ref "U4") (pin "25") (pinfunction "GND_25") (pintype "passive"))
      (node (ref "USB_TTL") (pin "5") (pinfunction "GND_5") (pintype "passive"))
    )
    (net (code "127") (name "Net-(DS2-A)") (class "Default")
      (node (ref "DS2") (pin "1") (pinfunction "A_1") (pintype "passive"))
      (node (ref "R23") (pin "2") (pintype "passive"))
    )
    (net (code "128") (name "Net-(ENET2-LED(G)-)") (class "Default")
      (node (ref "ENET2") (pin "10") (pinfunction "LED(G)-_10") (pintype "passive"))
      (node (ref "R17") (pin "1") (pintype "passive"))
    )
    (net (code "129") (name "Net-(ENET2-LED(Y)-)") (class "Default")
      (node (ref "ENET2") (pin "11") (pinfunction "LED(Y)-_11") (pintype "passive"))
      (node (ref "R18") (pin "1") (pintype "passive"))
    )
    (net (code "130") (name "Net-(ENET2-RCT)") (class "Default")
      (node (ref "C23") (pin "2") (pintype "passive"))
      (node (ref "ENET2") (pin "5") (pinfunction "RCT_5") (pintype "passive"))
    )
    (net (code "131") (name "Net-(ENET2-TCT)") (class "Default")
      (node (ref "C22") (pin "2") (pintype "passive"))
      (node (ref "ENET2") (pin "4") (pinfunction "TCT_4") (pintype "passive"))
    )
    (net (code "132") (name "Net-(PWR-A)") (class "Default")
      (node (ref "PWR") (pin "1") (pinfunction "A_1") (pintype "passive"))
      (node (ref "R3") (pin "1") (pintype "passive"))
    )
    (net (code "133") (name "Net-(U1-EN)") (class "Default")
      (node (ref "R1") (pin "1") (pintype "passive"))
      (node (ref "U1") (pin "4") (pinfunction "EN_4") (pintype "passive"))
    )
    (net (code "134") (name "Net-(U1-SET)") (class "Default")
      (node (ref "R2") (pin "1") (pintype "passive"))
      (node (ref "U1") (pin "3") (pinfunction "SET_3") (pintype "passive"))
    )
    (net (code "135") (name "Net-(U2-BS)") (class "Default")
      (node (ref "C5") (pin "1") (pintype "passive"))
      (node (ref "U2") (pin "6") (pinfunction "BS_6") (pintype "passive"))
    )
    (net (code "136") (name "Net-(U2-EN)") (class "Default")
      (node (ref "R6") (pin "2") (pintype "passive"))
      (node (ref "U2") (pin "5") (pinfunction "EN_5") (pintype "passive"))
    )
    (net (code "137") (name "Net-(U2-FB)") (class "Default")
      (node (ref "C6") (pin "2") (pintype "passive"))
      (node (ref "R4") (pin "2") (pintype "passive"))
      (node (ref "R5") (pin "2") (pintype "passive"))
      (node (ref "U2") (pin "4") (pinfunction "FB_4") (pintype "passive"))
    )
    (net (code "138") (name "Net-(U2-SW)") (class "Default")
      (node (ref "1") (pin "2") (pinfunction "2_2") (pintype "passive"))
      (node (ref "C5") (pin "2") (pintype "passive"))
      (node (ref "U2") (pin "2") (pinfunction "SW_2") (pintype "passive"))
    )
    (net (code "139") (name "Net-(U3-V3)") (class "Default")
      (node (ref "C12") (pin "2") (pintype "passive"))
      (node (ref "U3") (pin "8") (pinfunction "V3_8") (pintype "passive"))
    )
    (net (code "140") (name "Net-(U4-RBIAS)") (class "Default")
      (node (ref "R12") (pin "2") (pintype "passive"))
      (node (ref "U4") (pin "24") (pinfunction "RBIAS_24") (pintype "passive"))
    )
    (net (code "141") (name "Net-(U4-VDDCR)") (class "Default")
      (node (ref "C17") (pin "2") (pintype "passive"))
      (node (ref "C18") (pin "2") (pintype "passive"))
      (node (ref "U4") (pin "6") (pinfunction "VDDCR_6") (pintype "passive"))
    )
    (net (code "142") (name "VCC_3V3") (class "Default")
      (node (ref "1") (pin "1") (pinfunction "1_1") (pintype "passive"))
      (node (ref "C14") (pin "2") (pintype "passive"))
      (node (ref "C6") (pin "1") (pintype "passive"))
      (node (ref "C7") (pin "1") (pinfunction "A_1") (pintype "passive"))
      (node (ref "C8") (pin "2") (pintype "passive"))
      (node (ref "C9") (pin "2") (pintype "passive"))
      (node (ref "L3") (pin "1") (pinfunction "1_1") (pintype "passive"))
      (node (ref "R19") (pin "1") (pintype "passive"))
      (node (ref "R20") (pin "1") (pintype "passive"))
      (node (ref "R21") (pin "1") (pintype "passive"))
      (node (ref "R22") (pin "1") (pintype "passive"))
      (node (ref "R23") (pin "1") (pintype "passive"))
      (node (ref "R5") (pin "1") (pintype "passive"))
    )
    (net (code "143") (name "VDD_COIN_3V") (class "Default")
      (node (ref "I.MX6UL_CORE") (pin "J1_42") (pinfunction "42_J1_42") (pintype "passive"))
    )
    (net (code "144") (name "VENET_3V3") (class "Default")
      (node (ref "C15") (pin "2") (pintype "passive"))
      (node (ref "C19") (pin "2") (pintype "passive"))
      (node (ref "C20") (pin "2") (pintype "passive"))
      (node (ref "C21") (pin "2") (pintype "passive"))
      (node (ref "ENET2") (pin "12") (pinfunction "LED(Y)+_12") (pintype "passive"))
      (node (ref "ENET2") (pin "9") (pinfunction "LED(G)+_9") (pintype "passive"))
      (node (ref "L3") (pin "2") (pinfunction "2_2") (pintype "passive"))
      (node (ref "R10") (pin "1") (pintype "passive"))
      (node (ref "R11") (pin "1") (pintype "passive"))
      (node (ref "R13") (pin "2") (pintype "passive"))
      (node (ref "R14") (pin "2") (pintype "passive"))
      (node (ref "R15") (pin "2") (pintype "passive"))
      (node (ref "R16") (pin "2") (pintype "passive"))
      (node (ref "R7") (pin "2") (pintype "passive"))
      (node (ref "R8") (pin "2") (pintype "passive"))
      (node (ref "R9") (pin "1") (pintype "passive"))
      (node (ref "U4") (pin "1") (pinfunction "VDD2A_1") (pintype "passive"))
      (node (ref "U4") (pin "19") (pinfunction "VDD1A_19") (pintype "passive"))
      (node (ref "U4") (pin "9") (pinfunction "VDDIO_9") (pintype "passive"))
    )
    (net (code "145") (name "VUSB") (class "Default")
      (node (ref "C10") (pin "2") (pintype "passive"))
      (node (ref "C11") (pin "2") (pintype "passive"))
      (node (ref "C2") (pin "2") (pintype "passive"))
      (node (ref "R1") (pin "2") (pintype "passive"))
      (node (ref "U1") (pin "5") (pinfunction "VIN_5") (pintype "passive"))
      (node (ref "U3") (pin "5") (pinfunction "VCC_5") (pintype "passive"))
      (node (ref "USB_TTL") (pin "1") (pinfunction "VCC_1") (pintype "passive"))
    )
    (net (code "146") (name "unconnected-(ENET2-NC-Pad7)") (class "Default")
      (node (ref "ENET2") (pin "7") (pinfunction "NC_7") (pintype "passive"))
    )
    (net (code "147") (name "unconnected-(U3-RTS#-Pad4)") (class "Default")
      (node (ref "U3") (pin "4") (pinfunction "RTS#_4") (pintype "passive"))
    )
    (net (code "148") (name "unconnected-(U4-XTAL2-Pad4)") (class "Default")
      (node (ref "U4") (pin "4") (pinfunction "XTAL2_4") (pintype "passive"))
    )
    (net (code "149") (name "unconnected-(USB_TTL-ID-Pad4)") (class "Default")
      (node (ref "USB_TTL") (pin "4") (pinfunction "ID_4") (pintype "passive"))
    )
  )
)
